# wand_io.net
KiCad netlist of a schematic drawn in EAGLE
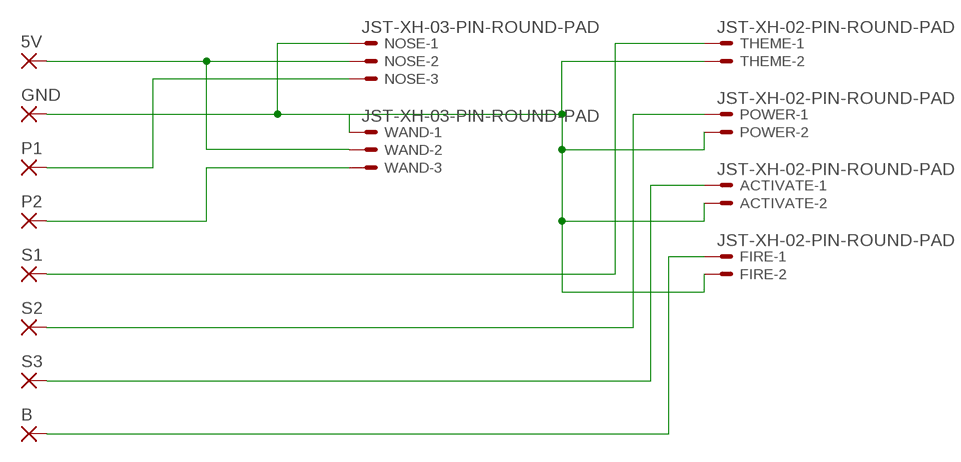
[diagram p0: schematic, sheet 1]

(export (version "E")
  (design (tool "Eeschema 10.0.6"))
  (components
    (comp (ref "5V")
      (value "2,54/1,1")
      (footprint "eagle-import:2,54_1,1")
      (libsource (lib "eagle-import") (part "2,54/1,1"))
    )
    (comp (ref "ACTIVATE")
      (value "JST-XH-02-PIN-ROUND-PAD")
      (footprint "eagle-import:JST-XH-02-PACKAGE-ROUND-PAD")
      (libsource (lib "eagle-import") (part "JST-XH-02-PIN-ROUND-PAD"))
    )
    (comp (ref "B")
      (value "2,54/1,1")
      (footprint "eagle-import:2,54_1,1")
      (libsource (lib "eagle-import") (part "2,54/1,1"))
    )
    (comp (ref "FIRE")
      (value "JST-XH-02-PIN-ROUND-PAD")
      (footprint "eagle-import:JST-XH-02-PACKAGE-ROUND-PAD")
      (libsource (lib "eagle-import") (part "JST-XH-02-PIN-ROUND-PAD"))
    )
    (comp (ref "GND")
      (value "2,54/1,1")
      (footprint "eagle-import:2,54_1,1")
      (libsource (lib "eagle-import") (part "2,54/1,1"))
    )
    (comp (ref "NOSE")
      (value "JST-XH-03-PIN-ROUND-PAD")
      (footprint "eagle-import:JST-XH-03-PACKAGE-ROUND-PAD")
      (libsource (lib "eagle-import") (part "JST-XH-03-PIN-ROUND-PAD"))
    )
    (comp (ref "P1")
      (value "2,54/1,1")
      (footprint "eagle-import:2,54_1,1")
      (libsource (lib "eagle-import") (part "2,54/1,1"))
    )
    (comp (ref "P2")
      (value "2,54/1,1")
      (footprint "eagle-import:2,54_1,1")
      (libsource (lib "eagle-import") (part "2,54/1,1"))
    )
    (comp (ref "POWER")
      (value "JST-XH-02-PIN-ROUND-PAD")
      (footprint "eagle-import:JST-XH-02-PACKAGE-ROUND-PAD")
      (libsource (lib "eagle-import") (part "JST-XH-02-PIN-ROUND-PAD"))
    )
    (comp (ref "S1")
      (value "2,54/1,1")
      (footprint "eagle-import:2,54_1,1")
      (libsource (lib "eagle-import") (part "2,54/1,1"))
    )
    (comp (ref "S2")
      (value "2,54/1,1")
      (footprint "eagle-import:2,54_1,1")
      (libsource (lib "eagle-import") (part "2,54/1,1"))
    )
    (comp (ref "S3")
      (value "2,54/1,1")
      (footprint "eagle-import:2,54_1,1")
      (libsource (lib "eagle-import") (part "2,54/1,1"))
    )
    (comp (ref "THEME")
      (value "JST-XH-02-PIN-ROUND-PAD")
      (footprint "eagle-import:JST-XH-02-PACKAGE-ROUND-PAD")
      (libsource (lib "eagle-import") (part "JST-XH-02-PIN-ROUND-PAD"))
    )
    (comp (ref "WAND")
      (value "JST-XH-03-PIN-ROUND-PAD")
      (footprint "eagle-import:JST-XH-03-PACKAGE-ROUND-PAD")
      (libsource (lib "eagle-import") (part "JST-XH-03-PIN-ROUND-PAD"))
    )
  )
  (nets
    (net (code "1") (name "Net-(5V-P)") (class "Default")
      (node (ref "5V") (pin "1") (pinfunction "P_1") (pintype "passive"))
      (node (ref "NOSE") (pin "2") (pinfunction "S_2") (pintype "passive"))
      (node (ref "WAND") (pin "2") (pinfunction "S_2") (pintype "passive"))
    )
    (net (code "2") (name "Net-(ACTIVATEA-S)") (class "Default")
      (node (ref "ACTIVATE") (pin "1") (pinfunction "S_1") (pintype "passive"))
      (node (ref "S3") (pin "1") (pinfunction "P_1") (pintype "passive"))
    )
    (net (code "3") (name "Net-(ACTIVATEB-S)") (class "Default")
      (node (ref "ACTIVATE") (pin "2") (pinfunction "S_2") (pintype "passive"))
      (node (ref "FIRE") (pin "2") (pinfunction "S_2") (pintype "passive"))
      (node (ref "GND") (pin "1") (pinfunction "P_1") (pintype "passive"))
      (node (ref "NOSE") (pin "1") (pinfunction "S_1") (pintype "passive"))
      (node (ref "POWER") (pin "2") (pinfunction "S_2") (pintype "passive"))
      (node (ref "THEME") (pin "2") (pinfunction "S_2") (pintype "passive"))
      (node (ref "WAND") (pin "1") (pinfunction "S_1") (pintype "passive"))
    )
    (net (code "4") (name "Net-(B-P)") (class "Default")
      (node (ref "B") (pin "1") (pinfunction "P_1") (pintype "passive"))
      (node (ref "FIRE") (pin "1") (pinfunction "S_1") (pintype "passive"))
    )
    (net (code "5") (name "Net-(NOSEC-S)") (class "Default")
      (node (ref "NOSE") (pin "3") (pinfunction "S_3") (pintype "passive"))
      (node (ref "P1") (pin "1") (pinfunction "P_1") (pintype "passive"))
    )
    (net (code "6") (name "Net-(P2-P)") (class "Default")
      (node (ref "P2") (pin "1") (pinfunction "P_1") (pintype "passive"))
      (node (ref "WAND") (pin "3") (pinfunction "S_3") (pintype "passive"))
    )
    (net (code "7") (name "Net-(POWERA-S)") (class "Default")
      (node (ref "POWER") (pin "1") (pinfunction "S_1") (pintype "passive"))
      (node (ref "S2") (pin "1") (pinfunction "P_1") (pintype "passive"))
    )
    (net (code "8") (name "Net-(S1-P)") (class "Default")
      (node (ref "S1") (pin "1") (pinfunction "P_1") (pintype "passive"))
      (node (ref "THEME") (pin "1") (pinfunction "S_1") (pintype "passive"))
    )
  )
)
